# IMU.net
KiCad netlist of a schematic drawn in Altium Designer
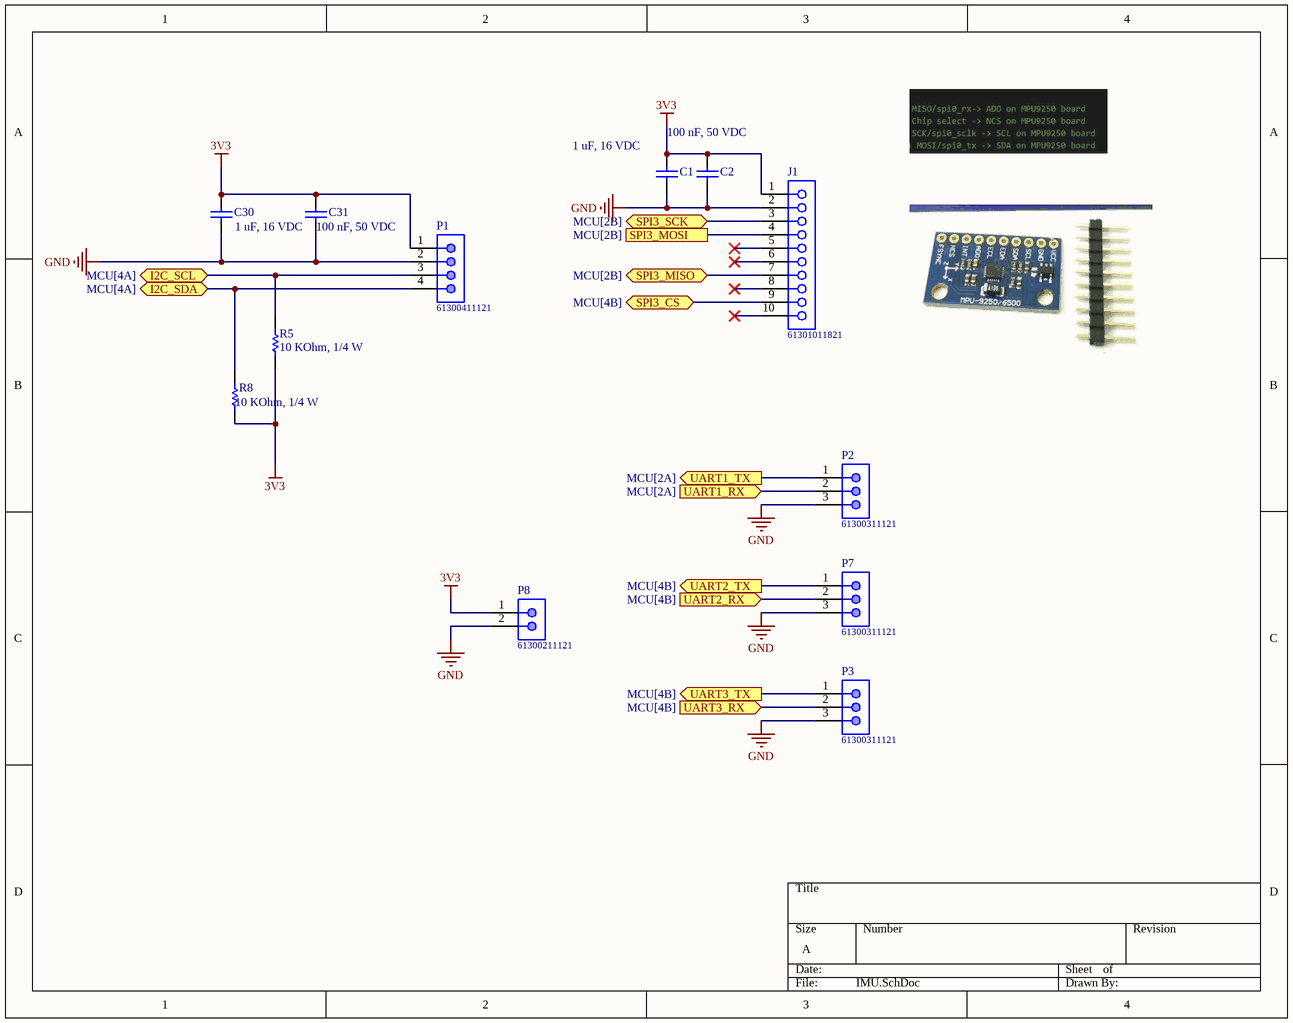
[diagram p0: IMU.SchDoc]

(export (version "E")
  (design (tool "Eeschema 10.0.6"))
  (components
    (comp (ref "C1")
      (value "1 uF, 16 VDC")
      (footprint "CAP_0603")
      (description "CAP, size 0603, 1 uF, 16 VDC")
      (fields (field (name "TOLERANCE") "+/-10%"))
      (libsource (lib "Altium_Ceramic_Cap") (part "0106031051016"))
    )
    (comp (ref "C2")
      (value "100 nF, 50 VDC")
      (footprint "CAP_0603")
      (description "CAP, size 0603, 100 nF, 50 VDC")
      (fields (field (name "TOLERANCE") "+/-10%"))
      (libsource (lib "Altium_Ceramic_Cap") (part "0106031041050"))
    )
    (comp (ref "C30")
      (value "1 uF, 16 VDC")
      (footprint "CAP_0603")
      (description "CAP, size 0603, 1 uF, 16 VDC")
      (fields (field (name "TOLERANCE") "+/-10%"))
      (libsource (lib "Altium_Ceramic_Cap") (part "0106031051016"))
    )
    (comp (ref "C31")
      (value "100 nF, 50 VDC")
      (footprint "CAP_0603")
      (description "CAP, size 0603, 100 nF, 50 VDC")
      (fields (field (name "TOLERANCE") "+/-10%"))
      (libsource (lib "Altium_Ceramic_Cap") (part "0106031041050"))
    )
    (comp (ref "J1")
      (value "61301011821")
      (footprint "61301011821")
      (description "WR-PHD Socket Header, THT, pitch 2.54mm, Single Row, Vertical, 10p")
      (fields (field (name "MANUFACTURER") "Wurth Elektronik"))
      (libsource (lib "Altium_Header") (part "61301011821"))
    )
    (comp (ref "P1")
      (value "61300411121")
      (footprint "61300411121")
      (description "WR-PHD Pin Header, THT, pitch 2.54mm, Single Row, Vertical, 4p")
      (fields (field (name "MANUFACTURER") "Wurth Elektronik"))
      (libsource (lib "Altium_Header") (part "61300411121"))
    )
    (comp (ref "P2")
      (value "61300311121")
      (footprint "61300311121")
      (description "WR-PHD Pin Header, THT, pitch 2.54mm, Single Row, Vertical, 3p")
      (fields (field (name "MANUFACTURER") "Wurth Elektronik"))
      (libsource (lib "Altium_Header") (part "61300311121"))
    )
    (comp (ref "P3")
      (value "61300311121")
      (footprint "61300311121")
      (description "WR-PHD Pin Header, THT, pitch 2.54mm, Single Row, Vertical, 3p")
      (fields (field (name "MANUFACTURER") "Wurth Elektronik"))
      (libsource (lib "Altium_Header") (part "61300311121"))
    )
    (comp (ref "P7")
      (value "61300311121")
      (footprint "61300311121")
      (description "WR-PHD Pin Header, THT, pitch 2.54mm, Single Row, Vertical, 3p")
      (fields (field (name "MANUFACTURER") "Wurth Elektronik"))
      (libsource (lib "Altium_Header") (part "61300311121"))
    )
    (comp (ref "P8")
      (value "61300211121")
      (footprint "61300211121")
      (description "WR-PHD Pin Header, THT, pitch 2.54mm, Single Row, Vertical, 2p")
      (fields (field (name "MANUFACTURER") "Wurth Elektronik"))
      (libsource (lib "Altium_Header") (part "61300211121"))
    )
    (comp (ref "R5")
      (value "10 KOhm, 1/4 W")
      (footprint "resistor_0603")
      (description "RES, size 0603, 10 KOhm, 1/4 W")
      (libsource (lib "Altium_Resistor") (part "0006031031"))
    )
    (comp (ref "R8")
      (value "10 KOhm, 1/4 W")
      (footprint "resistor_0603")
      (description "RES, size 0603, 10 KOhm, 1/4 W")
      (libsource (lib "Altium_Resistor") (part "0006031031"))
    )
  )
  (nets
    (net (code "1") (name "/I2C_SCL") (class "Default")
      (node (ref "P1") (pin "3") (pinfunction "3_3") (pintype "passive"))
      (node (ref "R5") (pin "2") (pinfunction "2_2") (pintype "passive"))
    )
    (net (code "2") (name "/I2C_SDA") (class "Default")
      (node (ref "P1") (pin "4") (pinfunction "4_4") (pintype "passive"))
      (node (ref "R8") (pin "2") (pinfunction "2_2") (pintype "passive"))
    )
    (net (code "3") (name "/SPI3_CS") (class "Default")
      (node (ref "J1") (pin "9") (pinfunction "9_9") (pintype "passive"))
    )
    (net (code "4") (name "/SPI3_MISO") (class "Default")
      (node (ref "J1") (pin "7") (pinfunction "7_7") (pintype "passive"))
    )
    (net (code "5") (name "/SPI3_MOSI") (class "Default")
      (node (ref "J1") (pin "4") (pinfunction "4_4") (pintype "passive"))
    )
    (net (code "6") (name "/SPI3_SCK") (class "Default")
      (node (ref "J1") (pin "3") (pinfunction "3_3") (pintype "passive"))
    )
    (net (code "7") (name "/UART1_RX") (class "Default")
      (node (ref "P2") (pin "2") (pinfunction "2_2") (pintype "passive"))
    )
    (net (code "8") (name "/UART1_TX") (class "Default")
      (node (ref "P2") (pin "1") (pinfunction "1_1") (pintype "passive"))
    )
    (net (code "9") (name "/UART2_RX") (class "Default")
      (node (ref "P7") (pin "2") (pinfunction "2_2") (pintype "passive"))
    )
    (net (code "10") (name "/UART2_TX") (class "Default")
      (node (ref "P7") (pin "1") (pinfunction "1_1") (pintype "passive"))
    )
    (net (code "11") (name "/UART3_RX") (class "Default")
      (node (ref "P3") (pin "2") (pinfunction "2_2") (pintype "passive"))
    )
    (net (code "12") (name "/UART3_TX") (class "Default")
      (node (ref "P3") (pin "1") (pinfunction "1_1") (pintype "passive"))
    )
    (net (code "13") (name "3V3") (class "Default")
      (node (ref "C1") (pin "2") (pinfunction "2_2") (pintype "passive"))
      (node (ref "C2") (pin "2") (pinfunction "2_2") (pintype "passive"))
      (node (ref "C30") (pin "2") (pinfunction "2_2") (pintype "passive"))
      (node (ref "C31") (pin "2") (pinfunction "2_2") (pintype "passive"))
      (node (ref "J1") (pin "1") (pinfunction "1_1") (pintype "passive"))
      (node (ref "P1") (pin "1") (pinfunction "1_1") (pintype "passive"))
      (node (ref "P8") (pin "1") (pinfunction "1_1") (pintype "passive"))
      (node (ref "R5") (pin "1") (pinfunction "1_1") (pintype "passive"))
      (node (ref "R8") (pin "1") (pinfunction "1_1") (pintype "passive"))
    )
    (net (code "14") (name "GND") (class "Default")
      (node (ref "C1") (pin "1") (pinfunction "1_1") (pintype "passive"))
      (node (ref "C2") (pin "1") (pinfunction "1_1") (pintype "passive"))
      (node (ref "C30") (pin "1") (pinfunction "1_1") (pintype "passive"))
      (node (ref "C31") (pin "1") (pinfunction "1_1") (pintype "passive"))
      (node (ref "J1") (pin "2") (pinfunction "2_2") (pintype "passive"))
      (node (ref "P1") (pin "2") (pinfunction "2_2") (pintype "passive"))
      (node (ref "P2") (pin "3") (pinfunction "3_3") (pintype "passive"))
      (node (ref "P3") (pin "3") (pinfunction "3_3") (pintype "passive"))
      (node (ref "P7") (pin "3") (pinfunction "3_3") (pintype "passive"))
      (node (ref "P8") (pin "2") (pinfunction "2_2") (pintype "passive"))
    )
    (net (code "15") (name "unconnected-(J1-Pad5)") (class "Default")
      (node (ref "J1") (pin "5") (pinfunction "5_5") (pintype "passive+no_connect"))
    )
    (net (code "16") (name "unconnected-(J1-Pad6)") (class "Default")
      (node (ref "J1") (pin "6") (pinfunction "6_6") (pintype "passive+no_connect"))
    )
    (net (code "17") (name "unconnected-(J1-Pad8)") (class "Default")
      (node (ref "J1") (pin "8") (pinfunction "8_8") (pintype "passive+no_connect"))
    )
    (net (code "18") (name "unconnected-(J1-Pad10)") (class "Default")
      (node (ref "J1") (pin "10") (pinfunction "10_10") (pintype "passive+no_connect"))
    )
  )
)
